# Skaarhoj_BI8-2x4.net
KiCad netlist of a schematic drawn in EAGLE
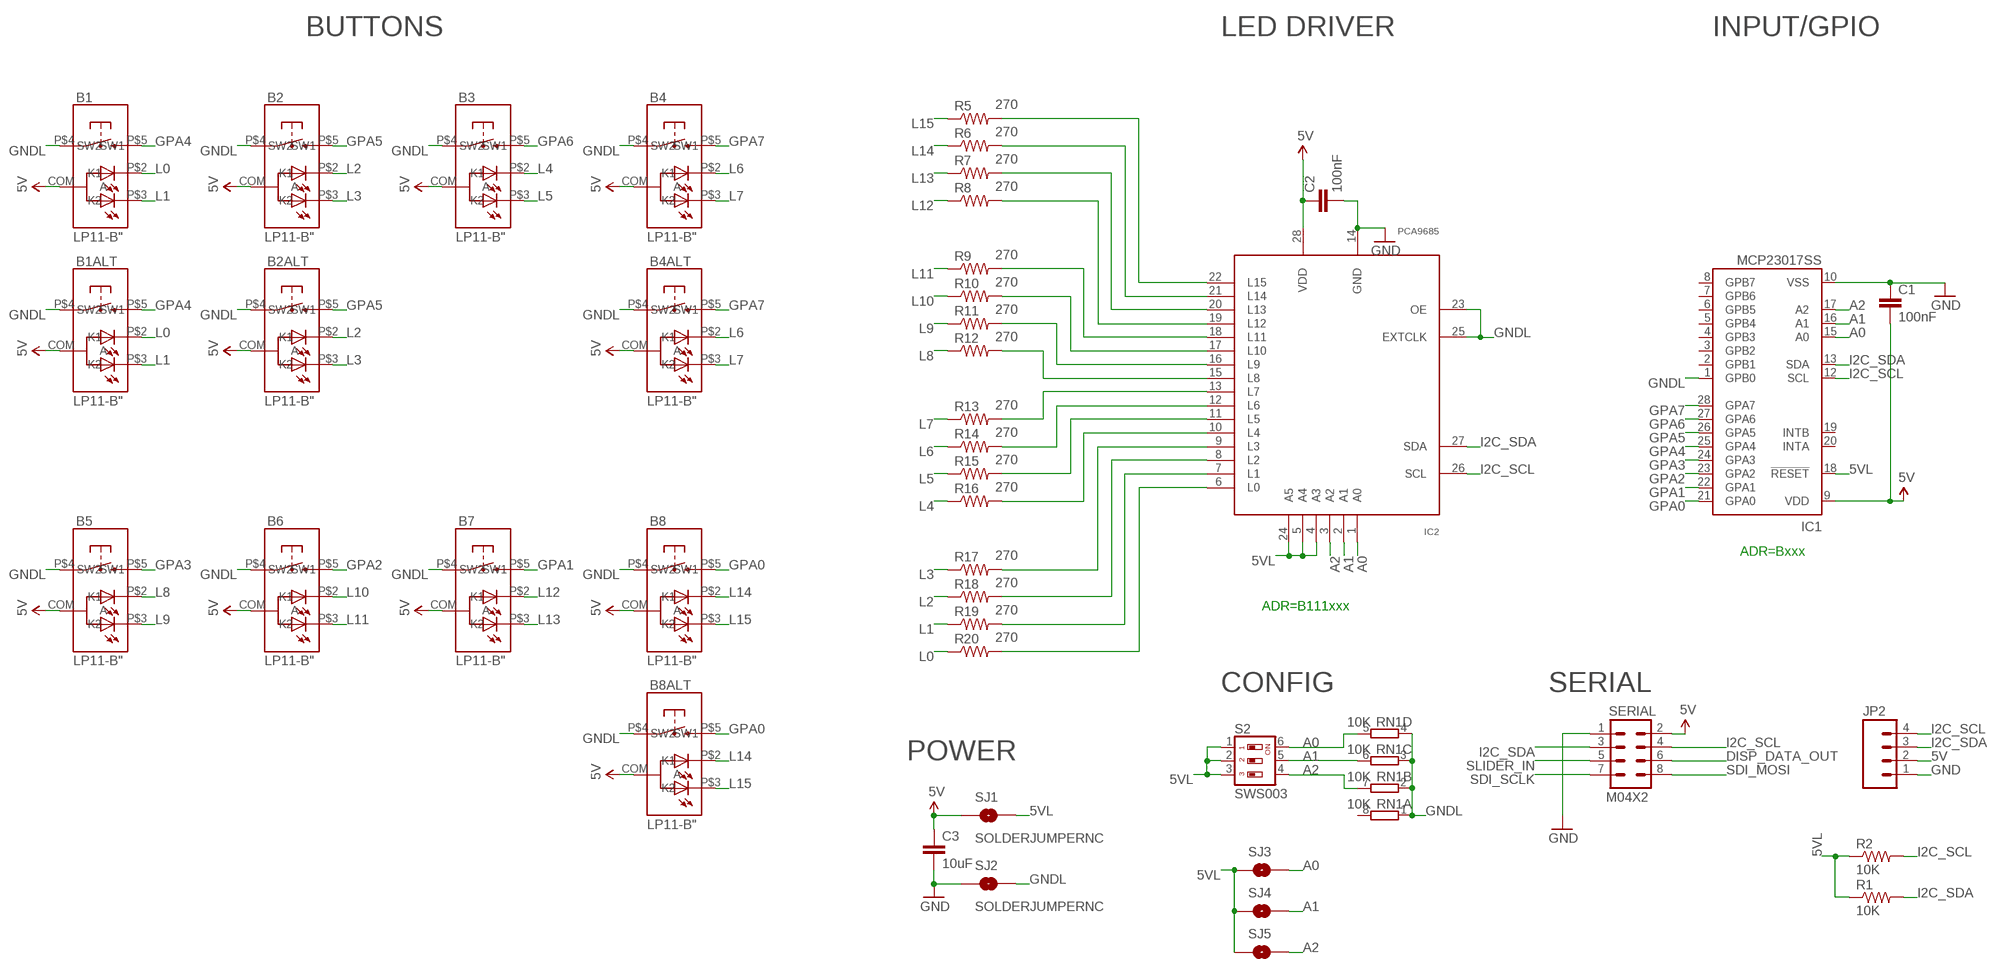
[diagram p0: schematic, sheet 1]

(export (version "E")
  (design (tool "Eeschema 10.0.6"))
  (components
    (comp (ref "B1")
      (value "LP11-B\"")
      (footprint "eagle-import:LP11")
      (libsource (lib "eagle-import") (part "LP11-B{dblquote}"))
    )
    (comp (ref "B1ALT")
      (value "LP11-B\"")
      (footprint "eagle-import:LP11")
      (libsource (lib "eagle-import") (part "LP11-B{dblquote}"))
    )
    (comp (ref "B2")
      (value "LP11-B\"")
      (footprint "eagle-import:LP11")
      (libsource (lib "eagle-import") (part "LP11-B{dblquote}"))
    )
    (comp (ref "B2ALT")
      (value "LP11-B\"")
      (footprint "eagle-import:LP11")
      (libsource (lib "eagle-import") (part "LP11-B{dblquote}"))
    )
    (comp (ref "B3")
      (value "LP11-B\"")
      (footprint "eagle-import:LP11")
      (libsource (lib "eagle-import") (part "LP11-B{dblquote}"))
    )
    (comp (ref "B4")
      (value "LP11-B\"")
      (footprint "eagle-import:LP11")
      (libsource (lib "eagle-import") (part "LP11-B{dblquote}"))
    )
    (comp (ref "B4ALT")
      (value "LP11-B\"")
      (footprint "eagle-import:LP11")
      (libsource (lib "eagle-import") (part "LP11-B{dblquote}"))
    )
    (comp (ref "B5")
      (value "LP11-B\"")
      (footprint "eagle-import:LP11")
      (libsource (lib "eagle-import") (part "LP11-B{dblquote}"))
    )
    (comp (ref "B6")
      (value "LP11-B\"")
      (footprint "eagle-import:LP11")
      (libsource (lib "eagle-import") (part "LP11-B{dblquote}"))
    )
    (comp (ref "B7")
      (value "LP11-B\"")
      (footprint "eagle-import:LP11")
      (libsource (lib "eagle-import") (part "LP11-B{dblquote}"))
    )
    (comp (ref "B8")
      (value "LP11-B\"")
      (footprint "eagle-import:LP11")
      (libsource (lib "eagle-import") (part "LP11-B{dblquote}"))
    )
    (comp (ref "B8ALT")
      (value "LP11-B\"")
      (footprint "eagle-import:LP11")
      (libsource (lib "eagle-import") (part "LP11-B{dblquote}"))
    )
    (comp (ref "C1")
      (value "100nF")
      (footprint "eagle-import:0603-CAP")
      (libsource (lib "eagle-import") (part "CAP0603-CAP"))
    )
    (comp (ref "C2")
      (value "100nF")
      (footprint "eagle-import:0603-CAP")
      (libsource (lib "eagle-import") (part "CAP0603-CAP"))
    )
    (comp (ref "C3")
      (value "10uF")
      (footprint "eagle-import:0805")
      (libsource (lib "eagle-import") (part "CAP0805"))
    )
    (comp (ref "IC1")
      (value "MCP23017SS")
      (footprint "eagle-import:SSOP28")
      (fields
        (field (name "MF") "MICROCHIP")
        (field (name "MPN") "MCP23017-E/SS")
        (field (name "MPN_1") "MCP23017-E/SS")
        (field (name "OC_FARNELL") "1467674")
        (field (name "OC_NEWARK") "31K2960")
      )
      (libsource (lib "eagle-import") (part "MCP23017SS"))
    )
    (comp (ref "IC2")
      (value "PCA9685")
      (footprint "eagle-import:TSSOP28")
      (libsource (lib "eagle-import") (part "PCA9685"))
    )
    (comp (ref "JP2")
      (value "M04PTH")
      (footprint "eagle-import:1X04")
      (libsource (lib "eagle-import") (part "M04PTH"))
    )
    (comp (ref "R1")
      (value "10K")
      (footprint "eagle-import:0603-RES")
      (libsource (lib "eagle-import") (part "RESISTOR0603-RES"))
    )
    (comp (ref "R2")
      (value "10K")
      (footprint "eagle-import:0603-RES")
      (libsource (lib "eagle-import") (part "RESISTOR0603-RES"))
    )
    (comp (ref "R5")
      (value "270")
      (footprint "eagle-import:0603-RES")
      (libsource (lib "eagle-import") (part "RESISTOR0603-RES"))
    )
    (comp (ref "R6")
      (value "270")
      (footprint "eagle-import:0603-RES")
      (libsource (lib "eagle-import") (part "RESISTOR0603-RES"))
    )
    (comp (ref "R7")
      (value "270")
      (footprint "eagle-import:0603-RES")
      (libsource (lib "eagle-import") (part "RESISTOR0603-RES"))
    )
    (comp (ref "R8")
      (value "270")
      (footprint "eagle-import:0603-RES")
      (libsource (lib "eagle-import") (part "RESISTOR0603-RES"))
    )
    (comp (ref "R9")
      (value "270")
      (footprint "eagle-import:0603-RES")
      (libsource (lib "eagle-import") (part "RESISTOR0603-RES"))
    )
    (comp (ref "R10")
      (value "270")
      (footprint "eagle-import:0603-RES")
      (libsource (lib "eagle-import") (part "RESISTOR0603-RES"))
    )
    (comp (ref "R11")
      (value "270")
      (footprint "eagle-import:0603-RES")
      (libsource (lib "eagle-import") (part "RESISTOR0603-RES"))
    )
    (comp (ref "R12")
      (value "270")
      (footprint "eagle-import:0603-RES")
      (libsource (lib "eagle-import") (part "RESISTOR0603-RES"))
    )
    (comp (ref "R13")
      (value "270")
      (footprint "eagle-import:0603-RES")
      (libsource (lib "eagle-import") (part "RESISTOR0603-RES"))
    )
    (comp (ref "R14")
      (value "270")
      (footprint "eagle-import:0603-RES")
      (libsource (lib "eagle-import") (part "RESISTOR0603-RES"))
    )
    (comp (ref "R15")
      (value "270")
      (footprint "eagle-import:0603-RES")
      (libsource (lib "eagle-import") (part "RESISTOR0603-RES"))
    )
    (comp (ref "R16")
      (value "270")
      (footprint "eagle-import:0603-RES")
      (libsource (lib "eagle-import") (part "RESISTOR0603-RES"))
    )
    (comp (ref "R17")
      (value "270")
      (footprint "eagle-import:0603-RES")
      (libsource (lib "eagle-import") (part "RESISTOR0603-RES"))
    )
    (comp (ref "R18")
      (value "270")
      (footprint "eagle-import:0603-RES")
      (libsource (lib "eagle-import") (part "RESISTOR0603-RES"))
    )
    (comp (ref "R19")
      (value "270")
      (footprint "eagle-import:0603-RES")
      (libsource (lib "eagle-import") (part "RESISTOR0603-RES"))
    )
    (comp (ref "R20")
      (value "270")
      (footprint "eagle-import:0603-RES")
      (libsource (lib "eagle-import") (part "RESISTOR0603-RES"))
    )
    (comp (ref "RN1")
      (value "10K")
      (footprint "eagle-import:CAY16_HAND")
      (libsource (lib "eagle-import") (part "4R-NCAY16"))
    )
    (comp (ref "S2")
      (value "SWS003")
      (footprint "eagle-import:SMS-003")
      (libsource (lib "eagle-import") (part "SWS003"))
    )
    (comp (ref "SERIAL")
      (value "M04X2")
      (footprint "eagle-import:2X4")
      (libsource (lib "eagle-import") (part "M04X2"))
    )
    (comp (ref "SJ1")
      (value "SOLDERJUMPERNC")
      (footprint "eagle-import:SJ_2S")
      (libsource (lib "eagle-import") (part "SOLDERJUMPERNC"))
    )
    (comp (ref "SJ2")
      (value "SOLDERJUMPERNC")
      (footprint "eagle-import:SJ_2S")
      (libsource (lib "eagle-import") (part "SOLDERJUMPERNC"))
    )
    (comp (ref "SJ3")
      (value "SOLDERJUMPERNC")
      (footprint "eagle-import:SJ_2S")
      (libsource (lib "eagle-import") (part "SOLDERJUMPERNC"))
    )
    (comp (ref "SJ4")
      (value "SOLDERJUMPERNC")
      (footprint "eagle-import:SJ_2S")
      (libsource (lib "eagle-import") (part "SOLDERJUMPERNC"))
    )
    (comp (ref "SJ5")
      (value "SOLDERJUMPERNC")
      (footprint "eagle-import:SJ_2S")
      (libsource (lib "eagle-import") (part "SOLDERJUMPERNC"))
    )
  )
  (nets
    (net (code "1") (name "/5VL") (class "Default")
      (node (ref "IC1") (pin "18") (pinfunction "~{RESET}_18") (pintype "input"))
      (node (ref "IC2") (pin "24") (pinfunction "A5_24") (pintype "input"))
      (node (ref "IC2") (pin "4") (pinfunction "A3_4") (pintype "input"))
      (node (ref "IC2") (pin "5") (pinfunction "A4_5") (pintype "input"))
      (node (ref "R1") (pin "1") (pinfunction "1_1") (pintype "passive"))
      (node (ref "R2") (pin "1") (pinfunction "1_1") (pintype "passive"))
      (node (ref "S2") (pin "1") (pinfunction "1_1") (pintype "passive"))
      (node (ref "S2") (pin "2") (pinfunction "2_2") (pintype "passive"))
      (node (ref "S2") (pin "3") (pinfunction "3_3") (pintype "passive"))
      (node (ref "SJ1") (pin "2") (pinfunction "2_2") (pintype "passive"))
      (node (ref "SJ3") (pin "1") (pinfunction "1_1") (pintype "passive"))
      (node (ref "SJ4") (pin "1") (pinfunction "1_1") (pintype "passive"))
      (node (ref "SJ5") (pin "1") (pinfunction "1_1") (pintype "passive"))
    )
    (net (code "2") (name "/A0") (class "Default")
      (node (ref "IC1") (pin "15") (pinfunction "A0_15") (pintype "input"))
      (node (ref "IC2") (pin "1") (pinfunction "A0_1") (pintype "input"))
      (node (ref "RN1") (pin "5") (pinfunction "2_5") (pintype "passive"))
      (node (ref "S2") (pin "6") (pinfunction "6_6") (pintype "passive"))
      (node (ref "SJ3") (pin "2") (pinfunction "2_2") (pintype "passive"))
    )
    (net (code "3") (name "/A1") (class "Default")
      (node (ref "IC1") (pin "16") (pinfunction "A1_16") (pintype "input"))
      (node (ref "IC2") (pin "2") (pinfunction "A1_2") (pintype "input"))
      (node (ref "RN1") (pin "6") (pinfunction "2_6") (pintype "passive"))
      (node (ref "S2") (pin "5") (pinfunction "5_5") (pintype "passive"))
      (node (ref "SJ4") (pin "2") (pinfunction "2_2") (pintype "passive"))
    )
    (net (code "4") (name "/A2") (class "Default")
      (node (ref "IC1") (pin "17") (pinfunction "A2_17") (pintype "input"))
      (node (ref "IC2") (pin "3") (pinfunction "A2_3") (pintype "input"))
      (node (ref "RN1") (pin "7") (pinfunction "2_7") (pintype "passive"))
      (node (ref "S2") (pin "4") (pinfunction "4_4") (pintype "passive"))
      (node (ref "SJ5") (pin "2") (pinfunction "2_2") (pintype "passive"))
    )
    (net (code "5") (name "/DISP_DATA_OUT") (class "Default")
      (node (ref "SERIAL") (pin "6") (pinfunction "6_6") (pintype "passive"))
    )
    (net (code "6") (name "/GNDL") (class "Default")
      (node (ref "B1") (pin "P$4") (pinfunction "SW1_P$4") (pintype "bidirectional"))
      (node (ref "B1ALT") (pin "P$4") (pinfunction "SW1_P$4") (pintype "bidirectional"))
      (node (ref "B2") (pin "P$4") (pinfunction "SW1_P$4") (pintype "bidirectional"))
      (node (ref "B2ALT") (pin "P$4") (pinfunction "SW1_P$4") (pintype "bidirectional"))
      (node (ref "B3") (pin "P$4") (pinfunction "SW1_P$4") (pintype "bidirectional"))
      (node (ref "B4") (pin "P$4") (pinfunction "SW1_P$4") (pintype "bidirectional"))
      (node (ref "B4ALT") (pin "P$4") (pinfunction "SW1_P$4") (pintype "bidirectional"))
      (node (ref "B5") (pin "P$4") (pinfunction "SW1_P$4") (pintype "bidirectional"))
      (node (ref "B6") (pin "P$4") (pinfunction "SW1_P$4") (pintype "bidirectional"))
      (node (ref "B7") (pin "P$4") (pinfunction "SW1_P$4") (pintype "bidirectional"))
      (node (ref "B8") (pin "P$4") (pinfunction "SW1_P$4") (pintype "bidirectional"))
      (node (ref "B8ALT") (pin "P$4") (pinfunction "SW1_P$4") (pintype "bidirectional"))
      (node (ref "IC1") (pin "1") (pinfunction "GPB0_1") (pintype "bidirectional"))
      (node (ref "IC2") (pin "23") (pinfunction "OE_23") (pintype "input"))
      (node (ref "IC2") (pin "25") (pinfunction "EXTCLK_25") (pintype "input"))
      (node (ref "RN1") (pin "1") (pinfunction "1_1") (pintype "passive"))
      (node (ref "RN1") (pin "2") (pinfunction "1_2") (pintype "passive"))
      (node (ref "RN1") (pin "3") (pinfunction "1_3") (pintype "passive"))
      (node (ref "RN1") (pin "4") (pinfunction "1_4") (pintype "passive"))
      (node (ref "SJ2") (pin "2") (pinfunction "2_2") (pintype "passive"))
    )
    (net (code "7") (name "/GPA0") (class "Default")
      (node (ref "B8") (pin "P$5") (pinfunction "SW2_P$5") (pintype "bidirectional"))
      (node (ref "B8ALT") (pin "P$5") (pinfunction "SW2_P$5") (pintype "bidirectional"))
      (node (ref "IC1") (pin "21") (pinfunction "GPA0_21") (pintype "bidirectional"))
    )
    (net (code "8") (name "/GPA1") (class "Default")
      (node (ref "B7") (pin "P$5") (pinfunction "SW2_P$5") (pintype "bidirectional"))
      (node (ref "IC1") (pin "22") (pinfunction "GPA1_22") (pintype "bidirectional"))
    )
    (net (code "9") (name "/GPA2") (class "Default")
      (node (ref "B6") (pin "P$5") (pinfunction "SW2_P$5") (pintype "bidirectional"))
      (node (ref "IC1") (pin "23") (pinfunction "GPA2_23") (pintype "bidirectional"))
    )
    (net (code "10") (name "/GPA3") (class "Default")
      (node (ref "B5") (pin "P$5") (pinfunction "SW2_P$5") (pintype "bidirectional"))
      (node (ref "IC1") (pin "24") (pinfunction "GPA3_24") (pintype "bidirectional"))
    )
    (net (code "11") (name "/GPA4") (class "Default")
      (node (ref "B1") (pin "P$5") (pinfunction "SW2_P$5") (pintype "bidirectional"))
      (node (ref "B1ALT") (pin "P$5") (pinfunction "SW2_P$5") (pintype "bidirectional"))
      (node (ref "IC1") (pin "25") (pinfunction "GPA4_25") (pintype "bidirectional"))
    )
    (net (code "12") (name "/GPA5") (class "Default")
      (node (ref "B2") (pin "P$5") (pinfunction "SW2_P$5") (pintype "bidirectional"))
      (node (ref "B2ALT") (pin "P$5") (pinfunction "SW2_P$5") (pintype "bidirectional"))
      (node (ref "IC1") (pin "26") (pinfunction "GPA5_26") (pintype "bidirectional"))
    )
    (net (code "13") (name "/GPA6") (class "Default")
      (node (ref "B3") (pin "P$5") (pinfunction "SW2_P$5") (pintype "bidirectional"))
      (node (ref "IC1") (pin "27") (pinfunction "GPA6_27") (pintype "bidirectional"))
    )
    (net (code "14") (name "/GPA7") (class "Default")
      (node (ref "B4") (pin "P$5") (pinfunction "SW2_P$5") (pintype "bidirectional"))
      (node (ref "B4ALT") (pin "P$5") (pinfunction "SW2_P$5") (pintype "bidirectional"))
      (node (ref "IC1") (pin "28") (pinfunction "GPA7_28") (pintype "bidirectional"))
    )
    (net (code "15") (name "/I2C_SCL") (class "Default")
      (node (ref "IC1") (pin "12") (pinfunction "SCL_12") (pintype "input"))
      (node (ref "IC2") (pin "26") (pinfunction "SCL_26") (pintype "input"))
      (node (ref "JP2") (pin "4") (pinfunction "4_4") (pintype "passive"))
      (node (ref "R2") (pin "2") (pinfunction "2_2") (pintype "passive"))
      (node (ref "SERIAL") (pin "4") (pinfunction "4_4") (pintype "passive"))
    )
    (net (code "16") (name "/I2C_SDA") (class "Default")
      (node (ref "IC1") (pin "13") (pinfunction "SDA_13") (pintype "bidirectional"))
      (node (ref "IC2") (pin "27") (pinfunction "SDA_27") (pintype "input"))
      (node (ref "JP2") (pin "3") (pinfunction "3_3") (pintype "passive"))
      (node (ref "R1") (pin "2") (pinfunction "2_2") (pintype "passive"))
      (node (ref "SERIAL") (pin "3") (pinfunction "3_3") (pintype "passive"))
    )
    (net (code "17") (name "/L0") (class "Default")
      (node (ref "B1") (pin "P$2") (pinfunction "K1_P$2") (pintype "bidirectional"))
      (node (ref "B1ALT") (pin "P$2") (pinfunction "K1_P$2") (pintype "bidirectional"))
      (node (ref "R20") (pin "1") (pinfunction "1_1") (pintype "passive"))
    )
    (net (code "18") (name "/L1") (class "Default")
      (node (ref "B1") (pin "P$3") (pinfunction "K2_P$3") (pintype "bidirectional"))
      (node (ref "B1ALT") (pin "P$3") (pinfunction "K2_P$3") (pintype "bidirectional"))
      (node (ref "R19") (pin "1") (pinfunction "1_1") (pintype "passive"))
    )
    (net (code "19") (name "/L2") (class "Default")
      (node (ref "B2") (pin "P$2") (pinfunction "K1_P$2") (pintype "bidirectional"))
      (node (ref "B2ALT") (pin "P$2") (pinfunction "K1_P$2") (pintype "bidirectional"))
      (node (ref "R18") (pin "1") (pinfunction "1_1") (pintype "passive"))
    )
    (net (code "20") (name "/L3") (class "Default")
      (node (ref "B2") (pin "P$3") (pinfunction "K2_P$3") (pintype "bidirectional"))
      (node (ref "B2ALT") (pin "P$3") (pinfunction "K2_P$3") (pintype "bidirectional"))
      (node (ref "R17") (pin "1") (pinfunction "1_1") (pintype "passive"))
    )
    (net (code "21") (name "/L4") (class "Default")
      (node (ref "B3") (pin "P$2") (pinfunction "K1_P$2") (pintype "bidirectional"))
      (node (ref "R16") (pin "1") (pinfunction "1_1") (pintype "passive"))
    )
    (net (code "22") (name "/L5") (class "Default")
      (node (ref "B3") (pin "P$3") (pinfunction "K2_P$3") (pintype "bidirectional"))
      (node (ref "R15") (pin "1") (pinfunction "1_1") (pintype "passive"))
    )
    (net (code "23") (name "/L6") (class "Default")
      (node (ref "B4") (pin "P$2") (pinfunction "K1_P$2") (pintype "bidirectional"))
      (node (ref "B4ALT") (pin "P$2") (pinfunction "K1_P$2") (pintype "bidirectional"))
      (node (ref "R14") (pin "1") (pinfunction "1_1") (pintype "passive"))
    )
    (net (code "24") (name "/L7") (class "Default")
      (node (ref "B4") (pin "P$3") (pinfunction "K2_P$3") (pintype "bidirectional"))
      (node (ref "B4ALT") (pin "P$3") (pinfunction "K2_P$3") (pintype "bidirectional"))
      (node (ref "R13") (pin "1") (pinfunction "1_1") (pintype "passive"))
    )
    (net (code "25") (name "/L8") (class "Default")
      (node (ref "B5") (pin "P$2") (pinfunction "K1_P$2") (pintype "bidirectional"))
      (node (ref "R12") (pin "1") (pinfunction "1_1") (pintype "passive"))
    )
    (net (code "26") (name "/L9") (class "Default")
      (node (ref "B5") (pin "P$3") (pinfunction "K2_P$3") (pintype "bidirectional"))
      (node (ref "R11") (pin "1") (pinfunction "1_1") (pintype "passive"))
    )
    (net (code "27") (name "/L10") (class "Default")
      (node (ref "B6") (pin "P$2") (pinfunction "K1_P$2") (pintype "bidirectional"))
      (node (ref "R10") (pin "1") (pinfunction "1_1") (pintype "passive"))
    )
    (net (code "28") (name "/L11") (class "Default")
      (node (ref "B6") (pin "P$3") (pinfunction "K2_P$3") (pintype "bidirectional"))
      (node (ref "R9") (pin "1") (pinfunction "1_1") (pintype "passive"))
    )
    (net (code "29") (name "/L12") (class "Default")
      (node (ref "B7") (pin "P$2") (pinfunction "K1_P$2") (pintype "bidirectional"))
      (node (ref "R8") (pin "1") (pinfunction "1_1") (pintype "passive"))
    )
    (net (code "30") (name "/L13") (class "Default")
      (node (ref "B7") (pin "P$3") (pinfunction "K2_P$3") (pintype "bidirectional"))
      (node (ref "R7") (pin "1") (pinfunction "1_1") (pintype "passive"))
    )
    (net (code "31") (name "/L14") (class "Default")
      (node (ref "B8") (pin "P$2") (pinfunction "K1_P$2") (pintype "bidirectional"))
      (node (ref "B8ALT") (pin "P$2") (pinfunction "K1_P$2") (pintype "bidirectional"))
      (node (ref "R6") (pin "1") (pinfunction "1_1") (pintype "passive"))
    )
    (net (code "32") (name "/L15") (class "Default")
      (node (ref "B8") (pin "P$3") (pinfunction "K2_P$3") (pintype "bidirectional"))
      (node (ref "B8ALT") (pin "P$3") (pinfunction "K2_P$3") (pintype "bidirectional"))
      (node (ref "R5") (pin "1") (pinfunction "1_1") (pintype "passive"))
    )
    (net (code "33") (name "/SDI_MOSI") (class "Default")
      (node (ref "SERIAL") (pin "8") (pinfunction "8_8") (pintype "passive"))
    )
    (net (code "34") (name "/SDI_SCLK") (class "Default")
      (node (ref "SERIAL") (pin "7") (pinfunction "7_7") (pintype "passive"))
    )
    (net (code "35") (name "/SLIDER_IN") (class "Default")
      (node (ref "SERIAL") (pin "5") (pinfunction "5_5") (pintype "passive"))
    )
    (net (code "36") (name "5V") (class "Default")
      (node (ref "B1") (pin "COM") (pinfunction "A_COM") (pintype "bidirectional"))
      (node (ref "B1ALT") (pin "COM") (pinfunction "A_COM") (pintype "bidirectional"))
      (node (ref "B2") (pin "COM") (pinfunction "A_COM") (pintype "bidirectional"))
      (node (ref "B2ALT") (pin "COM") (pinfunction "A_COM") (pintype "bidirectional"))
      (node (ref "B3") (pin "COM") (pinfunction "A_COM") (pintype "bidirectional"))
      (node (ref "B4") (pin "COM") (pinfunction "A_COM") (pintype "bidirectional"))
      (node (ref "B4ALT") (pin "COM") (pinfunction "A_COM") (pintype "bidirectional"))
      (node (ref "B5") (pin "COM") (pinfunction "A_COM") (pintype "bidirectional"))
      (node (ref "B6") (pin "COM") (pinfunction "A_COM") (pintype "bidirectional"))
      (node (ref "B7") (pin "COM") (pinfunction "A_COM") (pintype "bidirectional"))
      (node (ref "B8") (pin "COM") (pinfunction "A_COM") (pintype "bidirectional"))
      (node (ref "B8ALT") (pin "COM") (pinfunction "A_COM") (pintype "bidirectional"))
      (node (ref "C1") (pin "2") (pinfunction "2_2") (pintype "passive"))
      (node (ref "C2") (pin "1") (pinfunction "1_1") (pintype "passive"))
      (node (ref "C3") (pin "1") (pinfunction "1_1") (pintype "passive"))
      (node (ref "IC1") (pin "9") (pinfunction "VDD_9") (pintype "power_in"))
      (node (ref "IC2") (pin "28") (pinfunction "VDD_28") (pintype "power_in"))
      (node (ref "JP2") (pin "2") (pinfunction "2_2") (pintype "passive"))
      (node (ref "SERIAL") (pin "2") (pinfunction "2_2") (pintype "passive"))
      (node (ref "SJ1") (pin "1") (pinfunction "1_1") (pintype "passive"))
    )
    (net (code "37") (name "GND") (class "Default")
      (node (ref "C1") (pin "1") (pinfunction "1_1") (pintype "passive"))
      (node (ref "C2") (pin "2") (pinfunction "2_2") (pintype "passive"))
      (node (ref "C3") (pin "2") (pinfunction "2_2") (pintype "passive"))
      (node (ref "IC1") (pin "10") (pinfunction "VSS_10") (pintype "power_in"))
      (node (ref "IC2") (pin "14") (pinfunction "GND_14") (pintype "power_in"))
      (node (ref "JP2") (pin "1") (pinfunction "1_1") (pintype "passive"))
      (node (ref "SERIAL") (pin "1") (pinfunction "1_1") (pintype "passive"))
      (node (ref "SJ2") (pin "1") (pinfunction "1_1") (pintype "passive"))
    )
    (net (code "38") (name "Net-(IC2-L0)") (class "Default")
      (node (ref "IC2") (pin "6") (pinfunction "L0_6") (pintype "output"))
      (node (ref "R20") (pin "2") (pinfunction "2_2") (pintype "passive"))
    )
    (net (code "39") (name "Net-(IC2-L1)") (class "Default")
      (node (ref "IC2") (pin "7") (pinfunction "L1_7") (pintype "output"))
      (node (ref "R19") (pin "2") (pinfunction "2_2") (pintype "passive"))
    )
    (net (code "40") (name "Net-(IC2-L2)") (class "Default")
      (node (ref "IC2") (pin "8") (pinfunction "L2_8") (pintype "output"))
      (node (ref "R18") (pin "2") (pinfunction "2_2") (pintype "passive"))
    )
    (net (code "41") (name "Net-(IC2-L3)") (class "Default")
      (node (ref "IC2") (pin "9") (pinfunction "L3_9") (pintype "output"))
      (node (ref "R17") (pin "2") (pinfunction "2_2") (pintype "passive"))
    )
    (net (code "42") (name "Net-(IC2-L4)") (class "Default")
      (node (ref "IC2") (pin "10") (pinfunction "L4_10") (pintype "output"))
      (node (ref "R16") (pin "2") (pinfunction "2_2") (pintype "passive"))
    )
    (net (code "43") (name "Net-(IC2-L5)") (class "Default")
      (node (ref "IC2") (pin "11") (pinfunction "L5_11") (pintype "output"))
      (node (ref "R15") (pin "2") (pinfunction "2_2") (pintype "passive"))
    )
    (net (code "44") (name "Net-(IC2-L6)") (class "Default")
      (node (ref "IC2") (pin "12") (pinfunction "L6_12") (pintype "output"))
      (node (ref "R14") (pin "2") (pinfunction "2_2") (pintype "passive"))
    )
    (net (code "45") (name "Net-(IC2-L7)") (class "Default")
      (node (ref "IC2") (pin "13") (pinfunction "L7_13") (pintype "output"))
      (node (ref "R13") (pin "2") (pinfunction "2_2") (pintype "passive"))
    )
    (net (code "46") (name "Net-(IC2-L8)") (class "Default")
      (node (ref "IC2") (pin "15") (pinfunction "L8_15") (pintype "output"))
      (node (ref "R12") (pin "2") (pinfunction "2_2") (pintype "passive"))
    )
    (net (code "47") (name "Net-(IC2-L9)") (class "Default")
      (node (ref "IC2") (pin "16") (pinfunction "L9_16") (pintype "output"))
      (node (ref "R11") (pin "2") (pinfunction "2_2") (pintype "passive"))
    )
    (net (code "48") (name "Net-(IC2-L10)") (class "Default")
      (node (ref "IC2") (pin "17") (pinfunction "L10_17") (pintype "output"))
      (node (ref "R10") (pin "2") (pinfunction "2_2") (pintype "passive"))
    )
    (net (code "49") (name "Net-(IC2-L11)") (class "Default")
      (node (ref "IC2") (pin "18") (pinfunction "L11_18") (pintype "output"))
      (node (ref "R9") (pin "2") (pinfunction "2_2") (pintype "passive"))
    )
    (net (code "50") (name "Net-(IC2-L12)") (class "Default")
      (node (ref "IC2") (pin "19") (pinfunction "L12_19") (pintype "output"))
      (node (ref "R8") (pin "2") (pinfunction "2_2") (pintype "passive"))
    )
    (net (code "51") (name "Net-(IC2-L13)") (class "Default")
      (node (ref "IC2") (pin "20") (pinfunction "L13_20") (pintype "output"))
      (node (ref "R7") (pin "2") (pinfunction "2_2") (pintype "passive"))
    )
    (net (code "52") (name "Net-(IC2-L14)") (class "Default")
      (node (ref "IC2") (pin "21") (pinfunction "L14_21") (pintype "output"))
      (node (ref "R6") (pin "2") (pinfunction "2_2") (pintype "passive"))
    )
    (net (code "53") (name "Net-(IC2-L15)") (class "Default")
      (node (ref "IC2") (pin "22") (pinfunction "L15_22") (pintype "output"))
      (node (ref "R5") (pin "2") (pinfunction "2_2") (pintype "passive"))
    )
    (net (code "54") (name "unconnected-(IC1-GPB1-Pad2)") (class "Default")
      (node (ref "IC1") (pin "2") (pinfunction "GPB1_2") (pintype "bidirectional"))
    )
    (net (code "55") (name "unconnected-(IC1-GPB2-Pad3)") (class "Default")
      (node (ref "IC1") (pin "3") (pinfunction "GPB2_3") (pintype "bidirectional"))
    )
    (net (code "56") (name "unconnected-(IC1-GPB3-Pad4)") (class "Default")
      (node (ref "IC1") (pin "4") (pinfunction "GPB3_4") (pintype "bidirectional"))
    )
    (net (code "57") (name "unconnected-(IC1-GPB4-Pad5)") (class "Default")
      (node (ref "IC1") (pin "5") (pinfunction "GPB4_5") (pintype "bidirectional"))
    )
    (net (code "58") (name "unconnected-(IC1-GPB5-Pad6)") (class "Default")
      (node (ref "IC1") (pin "6") (pinfunction "GPB5_6") (pintype "bidirectional"))
    )
    (net (code "59") (name "unconnected-(IC1-GPB6-Pad7)") (class "Default")
      (node (ref "IC1") (pin "7") (pinfunction "GPB6_7") (pintype "bidirectional"))
    )
    (net (code "60") (name "unconnected-(IC1-GPB7-Pad8)") (class "Default")
      (node (ref "IC1") (pin "8") (pinfunction "GPB7_8") (pintype "bidirectional"))
    )
    (net (code "61") (name "unconnected-(IC1-INTA-Pad20)") (class "Default")
      (node (ref "IC1") (pin "20") (pinfunction "INTA_20") (pintype "output"))
    )
    (net (code "62") (name "unconnected-(IC1-INTB-Pad19)") (class "Default")
      (node (ref "IC1") (pin "19") (pinfunction "INTB_19") (pintype "output"))
    )
    (net (code "63") (name "unconnected-(RN1A-2-Pad8)") (class "Default")
      (node (ref "RN1") (pin "8") (pinfunction "2_8") (pintype "passive"))
    )
  )
)
